# sv20-mega.net
KiCad netlist of a schematic drawn in EAGLE
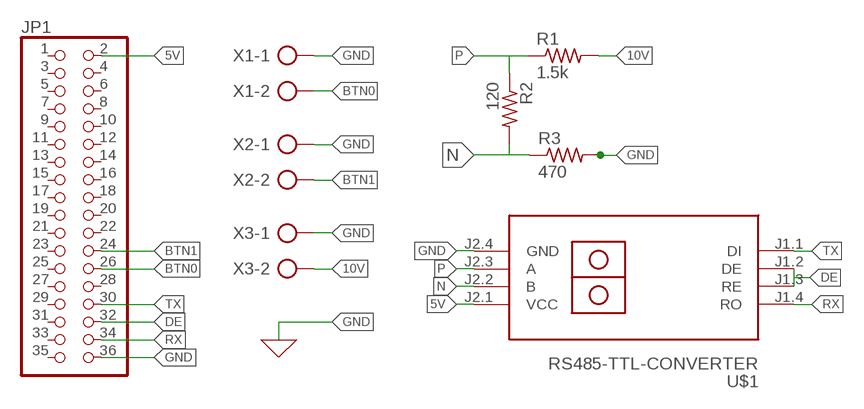
[diagram p0: schematic, sheet 1]

(export (version "E")
  (design (tool "Eeschema 10.0.6"))
  (components
    (comp (ref "JP1")
      (value "PINHD-2X18")
      (footprint "eagle-import:2X18")
      (libsource (lib "eagle-import") (part "PINHD-2X18"))
    )
    (comp (ref "R1")
      (value "1.5k")
      (footprint "eagle-import:0204_7")
      (libsource (lib "eagle-import") (part "R-US_0204/7"))
    )
    (comp (ref "R2")
      (value "120")
      (footprint "eagle-import:0204_7")
      (libsource (lib "eagle-import") (part "R-US_0204/7"))
    )
    (comp (ref "R3")
      (value "470")
      (footprint "eagle-import:0204_7")
      (libsource (lib "eagle-import") (part "R-US_0204/7"))
    )
    (comp (ref "U$1")
      (value "RS485-TTL-CONVERTER")
      (footprint "eagle-import:RS485-TTL-CONVERTER")
      (libsource (lib "eagle-import") (part "RS485-TTL-CONVERTER"))
    )
    (comp (ref "X1")
      (value "AK300/2")
      (footprint "eagle-import:AK300_2")
      (libsource (lib "eagle-import") (part "AK300/2"))
    )
    (comp (ref "X2")
      (value "AK300/2")
      (footprint "eagle-import:AK300_2")
      (libsource (lib "eagle-import") (part "AK300/2"))
    )
    (comp (ref "X3")
      (value "AK300/2")
      (footprint "eagle-import:AK300_2")
      (libsource (lib "eagle-import") (part "AK300/2"))
    )
  )
  (nets
    (net (code "1") (name "5V") (class "Default")
      (node (ref "JP1") (pin "2") (pinfunction "2_2") (pintype "passive"))
      (node (ref "U$1") (pin "J2.1") (pinfunction "VCC_J2.1") (pintype "power_in"))
    )
    (net (code "2") (name "10V") (class "Default")
      (node (ref "R1") (pin "2") (pinfunction "2_2") (pintype "passive"))
      (node (ref "X3") (pin "2") (pinfunction "KL_2") (pintype "passive"))
    )
    (net (code "3") (name "BTN0") (class "Default")
      (node (ref "JP1") (pin "26") (pinfunction "26_26") (pintype "passive"))
      (node (ref "X1") (pin "2") (pinfunction "KL_2") (pintype "passive"))
    )
    (net (code "4") (name "BTN1") (class "Default")
      (node (ref "JP1") (pin "24") (pinfunction "24_24") (pintype "passive"))
      (node (ref "X2") (pin "2") (pinfunction "KL_2") (pintype "passive"))
    )
    (net (code "5") (name "DE") (class "Default")
      (node (ref "JP1") (pin "32") (pinfunction "32_32") (pintype "passive"))
      (node (ref "U$1") (pin "J1.2") (pinfunction "DE_J1.2") (pintype "passive"))
      (node (ref "U$1") (pin "J1.3") (pinfunction "RE_J1.3") (pintype "passive"))
    )
    (net (code "6") (name "GND") (class "Default")
      (node (ref "JP1") (pin "36") (pinfunction "36_36") (pintype "passive"))
      (node (ref "R3") (pin "2") (pinfunction "2_2") (pintype "passive"))
      (node (ref "U$1") (pin "J2.4") (pinfunction "GND_J2.4") (pintype "power_in"))
      (node (ref "X1") (pin "1") (pinfunction "KL_1") (pintype "passive"))
      (node (ref "X2") (pin "1") (pinfunction "KL_1") (pintype "passive"))
      (node (ref "X3") (pin "1") (pinfunction "KL_1") (pintype "passive"))
    )
    (net (code "7") (name "N") (class "Default")
      (node (ref "R2") (pin "2") (pinfunction "2_2") (pintype "passive"))
      (node (ref "R3") (pin "1") (pinfunction "1_1") (pintype "passive"))
      (node (ref "U$1") (pin "J2.2") (pinfunction "B_J2.2") (pintype "passive"))
    )
    (net (code "8") (name "P") (class "Default")
      (node (ref "R1") (pin "1") (pinfunction "1_1") (pintype "passive"))
      (node (ref "R2") (pin "1") (pinfunction "1_1") (pintype "passive"))
      (node (ref "U$1") (pin "J2.3") (pinfunction "A_J2.3") (pintype "passive"))
    )
    (net (code "9") (name "RX") (class "Default")
      (node (ref "JP1") (pin "34") (pinfunction "34_34") (pintype "passive"))
      (node (ref "U$1") (pin "J1.4") (pinfunction "RO_J1.4") (pintype "passive"))
    )
    (net (code "10") (name "TX") (class "Default")
      (node (ref "JP1") (pin "30") (pinfunction "30_30") (pintype "passive"))
      (node (ref "U$1") (pin "J1.1") (pinfunction "DI_J1.1") (pintype "passive"))
    )
    (net (code "11") (name "unconnected-(JP1-Pad1)") (class "Default")
      (node (ref "JP1") (pin "1") (pinfunction "1_1") (pintype "passive"))
    )
    (net (code "12") (name "unconnected-(JP1-Pad3)") (class "Default")
      (node (ref "JP1") (pin "3") (pinfunction "3_3") (pintype "passive"))
    )
    (net (code "13") (name "unconnected-(JP1-Pad4)") (class "Default")
      (node (ref "JP1") (pin "4") (pinfunction "4_4") (pintype "passive"))
    )
    (net (code "14") (name "unconnected-(JP1-Pad5)") (class "Default")
      (node (ref "JP1") (pin "5") (pinfunction "5_5") (pintype "passive"))
    )
    (net (code "15") (name "unconnected-(JP1-Pad6)") (class "Default")
      (node (ref "JP1") (pin "6") (pinfunction "6_6") (pintype "passive"))
    )
    (net (code "16") (name "unconnected-(JP1-Pad7)") (class "Default")
      (node (ref "JP1") (pin "7") (pinfunction "7_7") (pintype "passive"))
    )
    (net (code "17") (name "unconnected-(JP1-Pad8)") (class "Default")
      (node (ref "JP1") (pin "8") (pinfunction "8_8") (pintype "passive"))
    )
    (net (code "18") (name "unconnected-(JP1-Pad9)") (class "Default")
      (node (ref "JP1") (pin "9") (pinfunction "9_9") (pintype "passive"))
    )
    (net (code "19") (name "unconnected-(JP1-Pad10)") (class "Default")
      (node (ref "JP1") (pin "10") (pinfunction "10_10") (pintype "passive"))
    )
    (net (code "20") (name "unconnected-(JP1-Pad11)") (class "Default")
      (node (ref "JP1") (pin "11") (pinfunction "11_11") (pintype "passive"))
    )
    (net (code "21") (name "unconnected-(JP1-Pad12)") (class "Default")
      (node (ref "JP1") (pin "12") (pinfunction "12_12") (pintype "passive"))
    )
    (net (code "22") (name "unconnected-(JP1-Pad13)") (class "Default")
      (node (ref "JP1") (pin "13") (pinfunction "13_13") (pintype "passive"))
    )
    (net (code "23") (name "unconnected-(JP1-Pad14)") (class "Default")
      (node (ref "JP1") (pin "14") (pinfunction "14_14") (pintype "passive"))
    )
    (net (code "24") (name "unconnected-(JP1-Pad15)") (class "Default")
      (node (ref "JP1") (pin "15") (pinfunction "15_15") (pintype "passive"))
    )
    (net (code "25") (name "unconnected-(JP1-Pad16)") (class "Default")
      (node (ref "JP1") (pin "16") (pinfunction "16_16") (pintype "passive"))
    )
    (net (code "26") (name "unconnected-(JP1-Pad17)") (class "Default")
      (node (ref "JP1") (pin "17") (pinfunction "17_17") (pintype "passive"))
    )
    (net (code "27") (name "unconnected-(JP1-Pad18)") (class "Default")
      (node (ref "JP1") (pin "18") (pinfunction "18_18") (pintype "passive"))
    )
    (net (code "28") (name "unconnected-(JP1-Pad19)") (class "Default")
      (node (ref "JP1") (pin "19") (pinfunction "19_19") (pintype "passive"))
    )
    (net (code "29") (name "unconnected-(JP1-Pad20)") (class "Default")
      (node (ref "JP1") (pin "20") (pinfunction "20_20") (pintype "passive"))
    )
    (net (code "30") (name "unconnected-(JP1-Pad21)") (class "Default")
      (node (ref "JP1") (pin "21") (pinfunction "21_21") (pintype "passive"))
    )
    (net (code "31") (name "unconnected-(JP1-Pad22)") (class "Default")
      (node (ref "JP1") (pin "22") (pinfunction "22_22") (pintype "passive"))
    )
    (net (code "32") (name "unconnected-(JP1-Pad23)") (class "Default")
      (node (ref "JP1") (pin "23") (pinfunction "23_23") (pintype "passive"))
    )
    (net (code "33") (name "unconnected-(JP1-Pad25)") (class "Default")
      (node (ref "JP1") (pin "25") (pinfunction "25_25") (pintype "passive"))
    )
    (net (code "34") (name "unconnected-(JP1-Pad27)") (class "Default")
      (node (ref "JP1") (pin "27") (pinfunction "27_27") (pintype "passive"))
    )
    (net (code "35") (name "unconnected-(JP1-Pad28)") (class "Default")
      (node (ref "JP1") (pin "28") (pinfunction "28_28") (pintype "passive"))
    )
    (net (code "36") (name "unconnected-(JP1-Pad29)") (class "Default")
      (node (ref "JP1") (pin "29") (pinfunction "29_29") (pintype "passive"))
    )
    (net (code "37") (name "unconnected-(JP1-Pad31)") (class "Default")
      (node (ref "JP1") (pin "31") (pinfunction "31_31") (pintype "passive"))
    )
    (net (code "38") (name "unconnected-(JP1-Pad33)") (class "Default")
      (node (ref "JP1") (pin "33") (pinfunction "33_33") (pintype "passive"))
    )
    (net (code "39") (name "unconnected-(JP1-Pad35)") (class "Default")
      (node (ref "JP1") (pin "35") (pinfunction "35_35") (pintype "passive"))
    )
  )
)
